# s1_sensor.net
KiCad netlist of a schematic drawn in Altium Designer
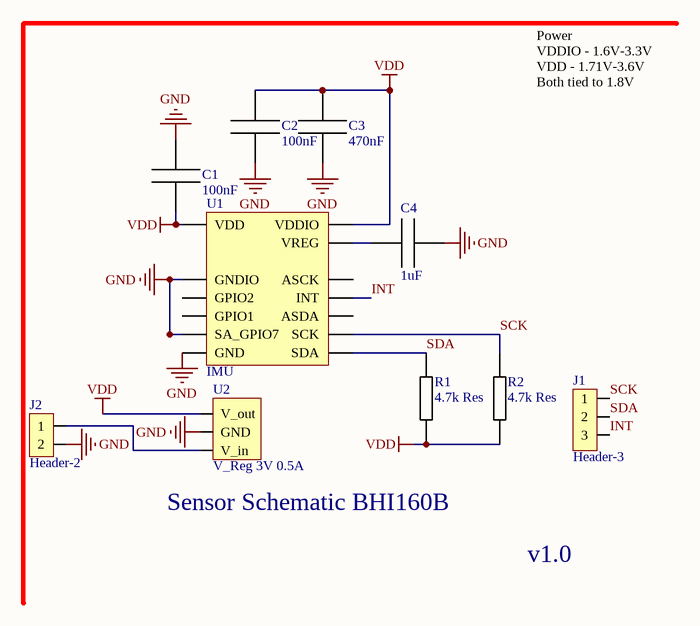
[diagram p0: s1_sensor.SchDoc]

(export (version "E")
  (design (tool "Eeschema 10.0.6"))
  (components
    (comp (ref "C1") (value "100nF") (footprint "0805 Passive") (libsource (lib "lib") (part "100nF")))
    (comp (ref "C2") (value "100nF") (footprint "0805 Passive") (libsource (lib "lib") (part "100nF")))
    (comp (ref "C3") (value "470nF") (footprint "0805 Passive") (libsource (lib "lib") (part "470nF")))
    (comp (ref "C4") (value "1uF") (footprint "0805 Passive") (libsource (lib "lib") (part "1uF")))
    (comp (ref "J1") (value "Header-3") (footprint "Header-3") (libsource (lib "lib") (part "Header 3-pin")))
    (comp (ref "J2") (value "Header-2") (footprint "Header-2") (libsource (lib "lib") (part "Header 2-pin")))
    (comp (ref "R1") (value "4.7k Res") (footprint "0805 Passive") (libsource (lib "lib") (part "4.7k Res")))
    (comp (ref "R2") (value "4.7k Res") (footprint "0805 Passive") (libsource (lib "lib") (part "4.7k Res")))
    (comp (ref "U1") (value "IMU") (footprint "BHI160b") (libsource (lib "lib") (part "BHI160B")))
    (comp (ref "U2") (value "V_Reg 3V 0.5A") (footprint "Header-3") (libsource (lib "lib") (part "V_Reg")))
  )
  (nets
    (net (code "1") (name "/INT") (class "Default")
      (node (ref "J1") (pin "3") (pinfunction "3_3") (pintype "passive"))
      (node (ref "U1") (pin "12") (pinfunction "INT_12") (pintype "passive"))
    )
    (net (code "2") (name "/SCK") (class "Default")
      (node (ref "J1") (pin "1") (pinfunction "1_1") (pintype "passive"))
      (node (ref "R2") (pin "2") (pinfunction "2_2") (pintype "passive"))
      (node (ref "U1") (pin "22") (pinfunction "SCK_22") (pintype "passive"))
    )
    (net (code "3") (name "/SDA") (class "Default")
      (node (ref "J1") (pin "2") (pinfunction "2_2") (pintype "passive"))
      (node (ref "R1") (pin "1") (pinfunction "1_1") (pintype "passive"))
      (node (ref "U1") (pin "24") (pinfunction "SDA_24") (pintype "passive"))
    )
    (net (code "4") (name "GND") (class "Default")
      (node (ref "C1") (pin "1") (pinfunction "1_1") (pintype "passive"))
      (node (ref "C2") (pin "0") (pinfunction "0_0") (pintype "passive"))
      (node (ref "C3") (pin "0") (pinfunction "0_0") (pintype "passive"))
      (node (ref "C4") (pin "1") (pinfunction "1_1") (pintype "passive"))
      (node (ref "J2") (pin "2") (pinfunction "2_2") (pintype "passive"))
      (node (ref "U1") (pin "18") (pinfunction "GND_18") (pintype "passive"))
      (node (ref "U1") (pin "20") (pinfunction "GNDIO_20") (pintype "passive"))
      (node (ref "U1") (pin "9") (pinfunction "SA_GPIO7_9") (pintype "passive"))
      (node (ref "U2") (pin "2") (pinfunction "GND_2") (pintype "passive"))
    )
    (net (code "5") (name "Net-(U1-VREG)") (class "Default")
      (node (ref "C4") (pin "0") (pinfunction "0_0") (pintype "passive"))
      (node (ref "U1") (pin "10") (pinfunction "VREG_10") (pintype "passive"))
    )
    (net (code "6") (name "Net-(U2-V_in)") (class "Default")
      (node (ref "J2") (pin "1") (pinfunction "1_1") (pintype "passive"))
      (node (ref "U2") (pin "1") (pinfunction "V_in_1") (pintype "passive"))
    )
    (net (code "7") (name "VDD") (class "Default")
      (node (ref "C1") (pin "0") (pinfunction "0_0") (pintype "passive"))
      (node (ref "C2") (pin "1") (pinfunction "1_1") (pintype "passive"))
      (node (ref "C3") (pin "1") (pinfunction "1_1") (pintype "passive"))
      (node (ref "R1") (pin "2") (pinfunction "2_2") (pintype "passive"))
      (node (ref "R2") (pin "1") (pinfunction "1_1") (pintype "passive"))
      (node (ref "U1") (pin "13") (pinfunction "VDD_13") (pintype "passive"))
      (node (ref "U1") (pin "8") (pinfunction "VDDIO_8") (pintype "passive"))
      (node (ref "U2") (pin "3") (pinfunction "V_out_3") (pintype "passive"))
    )
    (net (code "8") (name "unconnected-(U1-ASCK-Pad7)") (class "Default")
      (node (ref "U1") (pin "7") (pinfunction "ASCK_7") (pintype "passive"))
    )
    (net (code "9") (name "unconnected-(U1-ASDA-Pad21)") (class "Default")
      (node (ref "U1") (pin "21") (pinfunction "ASDA_21") (pintype "passive"))
    )
    (net (code "10") (name "unconnected-(U1-GPIO1-Pad3)") (class "Default")
      (node (ref "U1") (pin "3") (pinfunction "GPIO1_3") (pintype "passive"))
    )
    (net (code "11") (name "unconnected-(U1-GPIO2-Pad11)") (class "Default")
      (node (ref "U1") (pin "11") (pinfunction "GPIO2_11") (pintype "passive"))
    )
  )
)
